# cs301_YourGroupNumber.net
KiCad netlist of a schematic drawn in Altium Designer
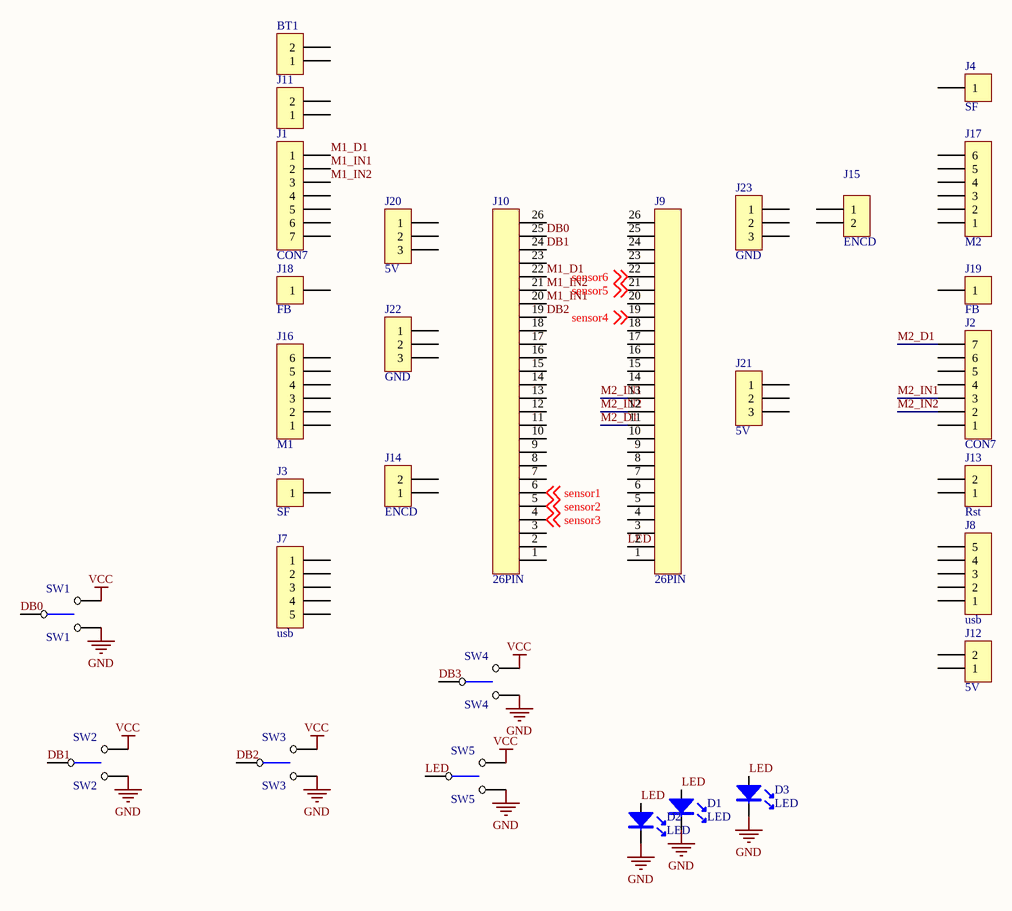
[diagram p0: cs301_YourGroupNumber.SchDoc]

(export (version "E")
  (design (tool "Eeschema 10.0.6"))
  (components
    (comp (ref "BT1")
      (value "Battery")
      (footprint "sip2")
      (description "Connector")
      (libsource (lib "") (part "CON2_1"))
    )
    (comp (ref "D1") (value "LED") (footprint "LED0.1/5MM") (libsource (lib "COMSYS301_2013") (part "LED")))
    (comp (ref "D2") (value "LED") (footprint "LED0.1/5MM") (libsource (lib "COMSYS301_2013") (part "LED")))
    (comp (ref "D3") (value "LED") (footprint "LED0.1/5MM") (libsource (lib "COMSYS301_2013") (part "LED")))
    (comp (ref "J1")
      (value "CON7")
      (footprint "SIP7")
      (description "Connector")
      (libsource (lib "Miscellaneous Devices") (part "CON7"))
    )
    (comp (ref "J2")
      (value "CON7")
      (footprint "SIP7")
      (description "Connector")
      (libsource (lib "") (part "CON7_1"))
    )
    (comp (ref "J3")
      (value "SF")
      (footprint "SIP1/0.6")
      (description "Connector")
      (libsource (lib "") (part "CON1_3"))
    )
    (comp (ref "J4")
      (value "SF")
      (footprint "SIP1/0.6")
      (description "Connector")
      (libsource (lib "") (part "CON1_1"))
    )
    (comp (ref "J7")
      (value "usb")
      (footprint "SIP5")
      (description "Connector")
      (libsource (lib "Miscellaneous Devices") (part "CON5"))
    )
    (comp (ref "J8")
      (value "usb")
      (footprint "SIP5")
      (description "Connector")
      (libsource (lib "") (part "CON5_1"))
    )
    (comp (ref "J9")
      (value "26PIN")
      (footprint "SIP26")
      (libsource (lib "Miscellaneous Devices") (part "26PIN"))
    )
    (comp (ref "J10") (value "26PIN") (footprint "SIP26") (libsource (lib "") (part "26PIN_1")))
    (comp (ref "J11")
      (value "Battery")
      (footprint "sip2")
      (description "Connector")
      (libsource (lib "") (part "CON2_1"))
    )
    (comp (ref "J12")
      (value "5V")
      (footprint "sip2")
      (description "Connector")
      (libsource (lib "") (part "CON2_2"))
    )
    (comp (ref "J13")
      (value "Rst")
      (footprint "sip2")
      (description "Connector")
      (libsource (lib "") (part "CON2_2"))
    )
    (comp (ref "J14")
      (value "ENCD")
      (footprint "sip2")
      (description "Connector")
      (libsource (lib "") (part "CON2_1"))
    )
    (comp (ref "J15")
      (value "ENCD")
      (footprint "sip2")
      (description "Connector")
      (libsource (lib "Miscellaneous Devices") (part "CON2"))
    )
    (comp (ref "J16")
      (value "M1")
      (footprint "sip6")
      (description "Connector")
      (libsource (lib "Miscellaneous Devices") (part "CON6"))
    )
    (comp (ref "J17")
      (value "M2")
      (footprint "sip6")
      (description "Connector")
      (libsource (lib "") (part "CON6_1"))
    )
    (comp (ref "J18")
      (value "FB")
      (footprint "SIP1/0.6")
      (description "Connector")
      (libsource (lib "") (part "CON1_2"))
    )
    (comp (ref "J19")
      (value "FB")
      (footprint "SIP1/0.6")
      (description "Connector")
      (libsource (lib "Miscellaneous Devices") (part "CON1"))
    )
    (comp (ref "J20")
      (value "5V")
      (footprint "sip3")
      (description "Connector")
      (libsource (lib "Miscellaneous Devices") (part "CON3"))
    )
    (comp (ref "J21")
      (value "5V")
      (footprint "sip3")
      (description "Connector")
      (libsource (lib "Miscellaneous Devices") (part "CON3"))
    )
    (comp (ref "J22")
      (value "GND")
      (footprint "sip3")
      (description "Connector")
      (libsource (lib "Miscellaneous Devices") (part "CON3"))
    )
    (comp (ref "J23")
      (value "GND")
      (footprint "sip3")
      (description "Connector")
      (libsource (lib "Miscellaneous Devices") (part "CON3"))
    )
    (comp (ref "SW1")
      (value "SW1")
      (footprint "SW-SPDT")
      (description "Toggle Switch")
      (libsource (lib "COMSYS301_2013") (part "SW-SPDT"))
    )
    (comp (ref "SW2")
      (value "SW2")
      (footprint "SW-SPDT")
      (description "Toggle Switch")
      (libsource (lib "COMSYS301_2013") (part "SW-SPDT"))
    )
    (comp (ref "SW3")
      (value "SW3")
      (footprint "SW-SPDT")
      (description "Toggle Switch")
      (libsource (lib "COMSYS301_2013") (part "SW-SPDT"))
    )
    (comp (ref "SW4")
      (value "SW4")
      (footprint "SW-SPDT")
      (description "Toggle Switch")
      (libsource (lib "COMSYS301_2013") (part "SW-SPDT"))
    )
    (comp (ref "SW5")
      (value "SW5")
      (footprint "SW-SPDT")
      (description "Toggle Switch")
      (libsource (lib "COMSYS301_2013") (part "SW-SPDT"))
    )
  )
  (nets
    (net (code "1") (name "/DB0") (class "Default")
      (node (ref "J10") (pin "25") (pinfunction "25_25") (pintype "passive"))
      (node (ref "SW1") (pin "2") (pinfunction "2_2") (pintype "passive"))
    )
    (net (code "2") (name "/DB1") (class "Default")
      (node (ref "J10") (pin "24") (pinfunction "24_24") (pintype "passive"))
      (node (ref "SW2") (pin "2") (pinfunction "2_2") (pintype "passive"))
    )
    (net (code "3") (name "/DB2") (class "Default")
      (node (ref "J10") (pin "19") (pinfunction "19_19") (pintype "passive"))
      (node (ref "SW3") (pin "2") (pinfunction "2_2") (pintype "passive"))
    )
    (net (code "4") (name "/DB3") (class "Default")
      (node (ref "SW4") (pin "2") (pinfunction "2_2") (pintype "passive"))
    )
    (net (code "5") (name "/LED") (class "Default")
      (node (ref "D1") (pin "A") (pinfunction "1_A") (pintype "passive"))
      (node (ref "D2") (pin "A") (pinfunction "1_A") (pintype "passive"))
      (node (ref "D3") (pin "A") (pinfunction "1_A") (pintype "passive"))
      (node (ref "J9") (pin "2") (pinfunction "2_2") (pintype "passive"))
      (node (ref "SW5") (pin "2") (pinfunction "2_2") (pintype "passive"))
    )
    (net (code "6") (name "/M1_D1") (class "Default")
      (node (ref "J1") (pin "1") (pinfunction "1_1") (pintype "passive"))
      (node (ref "J10") (pin "22") (pinfunction "22_22") (pintype "passive"))
    )
    (net (code "7") (name "/M1_IN1") (class "Default")
      (node (ref "J1") (pin "2") (pinfunction "2_2") (pintype "passive"))
      (node (ref "J10") (pin "20") (pinfunction "20_20") (pintype "passive"))
    )
    (net (code "8") (name "/M1_IN2") (class "Default")
      (node (ref "J1") (pin "3") (pinfunction "3_3") (pintype "passive"))
      (node (ref "J10") (pin "21") (pinfunction "21_21") (pintype "passive"))
    )
    (net (code "9") (name "/M2_D1") (class "Default")
      (node (ref "J2") (pin "7") (pinfunction "7_7") (pintype "passive"))
      (node (ref "J9") (pin "11") (pinfunction "11_11") (pintype "passive"))
    )
    (net (code "10") (name "/M2_IN1") (class "Default")
      (node (ref "J2") (pin "3") (pinfunction "3_3") (pintype "passive"))
      (node (ref "J9") (pin "13") (pinfunction "13_13") (pintype "passive"))
    )
    (net (code "11") (name "/M2_IN2") (class "Default")
      (node (ref "J2") (pin "2") (pinfunction "2_2") (pintype "passive"))
      (node (ref "J9") (pin "12") (pinfunction "12_12") (pintype "passive"))
    )
    (net (code "12") (name "GND") (class "Default")
      (node (ref "D1") (pin "K") (pinfunction "2_K") (pintype "passive"))
      (node (ref "D2") (pin "K") (pinfunction "2_K") (pintype "passive"))
      (node (ref "D3") (pin "K") (pinfunction "2_K") (pintype "passive"))
      (node (ref "SW1") (pin "3") (pinfunction "3_3") (pintype "passive"))
      (node (ref "SW2") (pin "3") (pinfunction "3_3") (pintype "passive"))
      (node (ref "SW3") (pin "3") (pinfunction "3_3") (pintype "passive"))
      (node (ref "SW4") (pin "3") (pinfunction "3_3") (pintype "passive"))
      (node (ref "SW5") (pin "3") (pinfunction "3_3") (pintype "passive"))
    )
    (net (code "13") (name "VCC") (class "Default")
      (node (ref "SW1") (pin "1") (pinfunction "1_1") (pintype "passive"))
      (node (ref "SW2") (pin "1") (pinfunction "1_1") (pintype "passive"))
      (node (ref "SW3") (pin "1") (pinfunction "1_1") (pintype "passive"))
      (node (ref "SW4") (pin "1") (pinfunction "1_1") (pintype "passive"))
      (node (ref "SW5") (pin "1") (pinfunction "1_1") (pintype "passive"))
    )
    (net (code "14") (name "sensor1") (class "Default")
      (node (ref "J10") (pin "6") (pinfunction "6_6") (pintype "passive"))
    )
    (net (code "15") (name "sensor2") (class "Default")
      (node (ref "J10") (pin "5") (pinfunction "5_5") (pintype "passive"))
    )
    (net (code "16") (name "sensor3") (class "Default")
      (node (ref "J10") (pin "4") (pinfunction "4_4") (pintype "passive"))
    )
    (net (code "17") (name "sensor4") (class "Default")
      (node (ref "J9") (pin "19") (pinfunction "19_19") (pintype "passive"))
    )
    (net (code "18") (name "sensor5") (class "Default")
      (node (ref "J9") (pin "21") (pinfunction "21_21") (pintype "passive"))
    )
    (net (code "19") (name "sensor6") (class "Default")
      (node (ref "J9") (pin "22") (pinfunction "22_22") (pintype "passive"))
    )
    (net (code "20") (name "unconnected-(BT1-Pad1)") (class "Default")
      (node (ref "BT1") (pin "1") (pinfunction "1_1") (pintype "passive"))
    )
    (net (code "21") (name "unconnected-(BT1-Pad2)") (class "Default")
      (node (ref "BT1") (pin "2") (pinfunction "2_2") (pintype "passive"))
    )
    (net (code "22") (name "unconnected-(J1-Pad4)") (class "Default")
      (node (ref "J1") (pin "4") (pinfunction "4_4") (pintype "passive"))
    )
    (net (code "23") (name "unconnected-(J1-Pad5)") (class "Default")
      (node (ref "J1") (pin "5") (pinfunction "5_5") (pintype "passive"))
    )
    (net (code "24") (name "unconnected-(J1-Pad6)") (class "Default")
      (node (ref "J1") (pin "6") (pinfunction "6_6") (pintype "passive"))
    )
    (net (code "25") (name "unconnected-(J1-Pad7)") (class "Default")
      (node (ref "J1") (pin "7") (pinfunction "7_7") (pintype "passive"))
    )
    (net (code "26") (name "unconnected-(J2-Pad1)") (class "Default")
      (node (ref "J2") (pin "1") (pinfunction "1_1") (pintype "passive"))
    )
    (net (code "27") (name "unconnected-(J2-Pad4)") (class "Default")
      (node (ref "J2") (pin "4") (pinfunction "4_4") (pintype "passive"))
    )
    (net (code "28") (name "unconnected-(J2-Pad5)") (class "Default")
      (node (ref "J2") (pin "5") (pinfunction "5_5") (pintype "passive"))
    )
    (net (code "29") (name "unconnected-(J2-Pad6)") (class "Default")
      (node (ref "J2") (pin "6") (pinfunction "6_6") (pintype "passive"))
    )
    (net (code "30") (name "unconnected-(J3-Pad1)") (class "Default")
      (node (ref "J3") (pin "1") (pinfunction "1_1") (pintype "passive"))
    )
    (net (code "31") (name "unconnected-(J4-Pad1)") (class "Default")
      (node (ref "J4") (pin "1") (pinfunction "1_1") (pintype "passive"))
    )
    (net (code "32") (name "unconnected-(J7-Pad1)") (class "Default")
      (node (ref "J7") (pin "1") (pinfunction "1_1") (pintype "passive"))
    )
    (net (code "33") (name "unconnected-(J7-Pad2)") (class "Default")
      (node (ref "J7") (pin "2") (pinfunction "2_2") (pintype "passive"))
    )
    (net (code "34") (name "unconnected-(J7-Pad3)") (class "Default")
      (node (ref "J7") (pin "3") (pinfunction "3_3") (pintype "passive"))
    )
    (net (code "35") (name "unconnected-(J7-Pad4)") (class "Default")
      (node (ref "J7") (pin "4") (pinfunction "4_4") (pintype "passive"))
    )
    (net (code "36") (name "unconnected-(J7-Pad5)") (class "Default")
      (node (ref "J7") (pin "5") (pinfunction "5_5") (pintype "passive"))
    )
    (net (code "37") (name "unconnected-(J8-Pad1)") (class "Default")
      (node (ref "J8") (pin "1") (pinfunction "1_1") (pintype "passive"))
    )
    (net (code "38") (name "unconnected-(J8-Pad2)") (class "Default")
      (node (ref "J8") (pin "2") (pinfunction "2_2") (pintype "passive"))
    )
    (net (code "39") (name "unconnected-(J8-Pad3)") (class "Default")
      (node (ref "J8") (pin "3") (pinfunction "3_3") (pintype "passive"))
    )
    (net (code "40") (name "unconnected-(J8-Pad4)") (class "Default")
      (node (ref "J8") (pin "4") (pinfunction "4_4") (pintype "passive"))
    )
    (net (code "41") (name "unconnected-(J8-Pad5)") (class "Default")
      (node (ref "J8") (pin "5") (pinfunction "5_5") (pintype "passive"))
    )
    (net (code "42") (name "unconnected-(J9-Pad1)") (class "Default")
      (node (ref "J9") (pin "1") (pinfunction "1_1") (pintype "passive"))
    )
    (net (code "43") (name "unconnected-(J9-Pad3)") (class "Default")
      (node (ref "J9") (pin "3") (pinfunction "3_3") (pintype "passive"))
    )
    (net (code "44") (name "unconnected-(J9-Pad4)") (class "Default")
      (node (ref "J9") (pin "4") (pinfunction "4_4") (pintype "passive"))
    )
    (net (code "45") (name "unconnected-(J9-Pad5)") (class "Default")
      (node (ref "J9") (pin "5") (pinfunction "5_5") (pintype "passive"))
    )
    (net (code "46") (name "unconnected-(J9-Pad6)") (class "Default")
      (node (ref "J9") (pin "6") (pinfunction "6_6") (pintype "passive"))
    )
    (net (code "47") (name "unconnected-(J9-Pad7)") (class "Default")
      (node (ref "J9") (pin "7") (pinfunction "7_7") (pintype "passive"))
    )
    (net (code "48") (name "unconnected-(J9-Pad8)") (class "Default")
      (node (ref "J9") (pin "8") (pinfunction "8_8") (pintype "passive"))
    )
    (net (code "49") (name "unconnected-(J9-Pad9)") (class "Default")
      (node (ref "J9") (pin "9") (pinfunction "9_9") (pintype "passive"))
    )
    (net (code "50") (name "unconnected-(J9-Pad10)") (class "Default")
      (node (ref "J9") (pin "10") (pinfunction "10_10") (pintype "passive"))
    )
    (net (code "51") (name "unconnected-(J9-Pad14)") (class "Default")
      (node (ref "J9") (pin "14") (pinfunction "14_14") (pintype "passive"))
    )
    (net (code "52") (name "unconnected-(J9-Pad15)") (class "Default")
      (node (ref "J9") (pin "15") (pinfunction "15_15") (pintype "passive"))
    )
    (net (code "53") (name "unconnected-(J9-Pad16)") (class "Default")
      (node (ref "J9") (pin "16") (pinfunction "16_16") (pintype "passive"))
    )
    (net (code "54") (name "unconnected-(J9-Pad17)") (class "Default")
      (node (ref "J9") (pin "17") (pinfunction "17_17") (pintype "passive"))
    )
    (net (code "55") (name "unconnected-(J9-Pad18)") (class "Default")
      (node (ref "J9") (pin "18") (pinfunction "18_18") (pintype "passive"))
    )
    (net (code "56") (name "unconnected-(J9-Pad20)") (class "Default")
      (node (ref "J9") (pin "20") (pinfunction "20_20") (pintype "passive"))
    )
    (net (code "57") (name "unconnected-(J9-Pad23)") (class "Default")
      (node (ref "J9") (pin "23") (pinfunction "23_23") (pintype "passive"))
    )
    (net (code "58") (name "unconnected-(J9-Pad24)") (class "Default")
      (node (ref "J9") (pin "24") (pinfunction "24_24") (pintype "passive"))
    )
    (net (code "59") (name "unconnected-(J9-Pad25)") (class "Default")
      (node (ref "J9") (pin "25") (pinfunction "25_25") (pintype "passive"))
    )
    (net (code "60") (name "unconnected-(J9-Pad26)") (class "Default")
      (node (ref "J9") (pin "26") (pinfunction "26_26") (pintype "passive"))
    )
    (net (code "61") (name "unconnected-(J10-Pad1)") (class "Default")
      (node (ref "J10") (pin "1") (pinfunction "1_1") (pintype "passive"))
    )
    (net (code "62") (name "unconnected-(J10-Pad2)") (class "Default")
      (node (ref "J10") (pin "2") (pinfunction "2_2") (pintype "passive"))
    )
    (net (code "63") (name "unconnected-(J10-Pad3)") (class "Default")
      (node (ref "J10") (pin "3") (pinfunction "3_3") (pintype "passive"))
    )
    (net (code "64") (name "unconnected-(J10-Pad7)") (class "Default")
      (node (ref "J10") (pin "7") (pinfunction "7_7") (pintype "passive"))
    )
    (net (code "65") (name "unconnected-(J10-Pad8)") (class "Default")
      (node (ref "J10") (pin "8") (pinfunction "8_8") (pintype "passive"))
    )
    (net (code "66") (name "unconnected-(J10-Pad9)") (class "Default")
      (node (ref "J10") (pin "9") (pinfunction "9_9") (pintype "passive"))
    )
    (net (code "67") (name "unconnected-(J10-Pad10)") (class "Default")
      (node (ref "J10") (pin "10") (pinfunction "10_10") (pintype "passive"))
    )
    (net (code "68") (name "unconnected-(J10-Pad11)") (class "Default")
      (node (ref "J10") (pin "11") (pinfunction "11_11") (pintype "passive"))
    )
    (net (code "69") (name "unconnected-(J10-Pad12)") (class "Default")
      (node (ref "J10") (pin "12") (pinfunction "12_12") (pintype "passive"))
    )
    (net (code "70") (name "unconnected-(J10-Pad13)") (class "Default")
      (node (ref "J10") (pin "13") (pinfunction "13_13") (pintype "passive"))
    )
    (net (code "71") (name "unconnected-(J10-Pad14)") (class "Default")
      (node (ref "J10") (pin "14") (pinfunction "14_14") (pintype "passive"))
    )
    (net (code "72") (name "unconnected-(J10-Pad15)") (class "Default")
      (node (ref "J10") (pin "15") (pinfunction "15_15") (pintype "passive"))
    )
    (net (code "73") (name "unconnected-(J10-Pad16)") (class "Default")
      (node (ref "J10") (pin "16") (pinfunction "16_16") (pintype "passive"))
    )
    (net (code "74") (name "unconnected-(J10-Pad17)") (class "Default")
      (node (ref "J10") (pin "17") (pinfunction "17_17") (pintype "passive"))
    )
    (net (code "75") (name "unconnected-(J10-Pad18)") (class "Default")
      (node (ref "J10") (pin "18") (pinfunction "18_18") (pintype "passive"))
    )
    (net (code "76") (name "unconnected-(J10-Pad23)") (class "Default")
      (node (ref "J10") (pin "23") (pinfunction "23_23") (pintype "passive"))
    )
    (net (code "77") (name "unconnected-(J10-Pad26)") (class "Default")
      (node (ref "J10") (pin "26") (pinfunction "26_26") (pintype "passive"))
    )
    (net (code "78") (name "unconnected-(J11-Pad1)") (class "Default")
      (node (ref "J11") (pin "1") (pinfunction "1_1") (pintype "passive"))
    )
    (net (code "79") (name "unconnected-(J11-Pad2)") (class "Default")
      (node (ref "J11") (pin "2") (pinfunction "2_2") (pintype "passive"))
    )
    (net (code "80") (name "unconnected-(J12-Pad1)") (class "Default")
      (node (ref "J12") (pin "1") (pinfunction "1_1") (pintype "passive"))
    )
    (net (code "81") (name "unconnected-(J12-Pad2)") (class "Default")
      (node (ref "J12") (pin "2") (pinfunction "2_2") (pintype "passive"))
    )
    (net (code "82") (name "unconnected-(J13-Pad1)") (class "Default")
      (node (ref "J13") (pin "1") (pinfunction "1_1") (pintype "passive"))
    )
    (net (code "83") (name "unconnected-(J13-Pad2)") (class "Default")
      (node (ref "J13") (pin "2") (pinfunction "2_2") (pintype "passive"))
    )
    (net (code "84") (name "unconnected-(J14-Pad1)") (class "Default")
      (node (ref "J14") (pin "1") (pinfunction "1_1") (pintype "passive"))
    )
    (net (code "85") (name "unconnected-(J14-Pad2)") (class "Default")
      (node (ref "J14") (pin "2") (pinfunction "2_2") (pintype "passive"))
    )
    (net (code "86") (name "unconnected-(J15-Pad1)") (class "Default")
      (node (ref "J15") (pin "1") (pinfunction "1_1") (pintype "passive"))
    )
    (net (code "87") (name "unconnected-(J15-Pad2)") (class "Default")
      (node (ref "J15") (pin "2") (pinfunction "2_2") (pintype "passive"))
    )
    (net (code "88") (name "unconnected-(J16-Pad1)") (class "Default")
      (node (ref "J16") (pin "1") (pinfunction "1_1") (pintype "passive"))
    )
    (net (code "89") (name "unconnected-(J16-Pad2)") (class "Default")
      (node (ref "J16") (pin "2") (pinfunction "2_2") (pintype "passive"))
    )
    (net (code "90") (name "unconnected-(J16-Pad3)") (class "Default")
      (node (ref "J16") (pin "3") (pinfunction "3_3") (pintype "passive"))
    )
    (net (code "91") (name "unconnected-(J16-Pad4)") (class "Default")
      (node (ref "J16") (pin "4") (pinfunction "4_4") (pintype "passive"))
    )
    (net (code "92") (name "unconnected-(J16-Pad5)") (class "Default")
      (node (ref "J16") (pin "5") (pinfunction "5_5") (pintype "passive"))
    )
    (net (code "93") (name "unconnected-(J16-Pad6)") (class "Default")
      (node (ref "J16") (pin "6") (pinfunction "6_6") (pintype "passive"))
    )
    (net (code "94") (name "unconnected-(J17-Pad1)") (class "Default")
      (node (ref "J17") (pin "1") (pinfunction "1_1") (pintype "passive"))
    )
    (net (code "95") (name "unconnected-(J17-Pad2)") (class "Default")
      (node (ref "J17") (pin "2") (pinfunction "2_2") (pintype "passive"))
    )
    (net (code "96") (name "unconnected-(J17-Pad3)") (class "Default")
      (node (ref "J17") (pin "3") (pinfunction "3_3") (pintype "passive"))
    )
    (net (code "97") (name "unconnected-(J17-Pad4)") (class "Default")
      (node (ref "J17") (pin "4") (pinfunction "4_4") (pintype "passive"))
    )
    (net (code "98") (name "unconnected-(J17-Pad5)") (class "Default")
      (node (ref "J17") (pin "5") (pinfunction "5_5") (pintype "passive"))
    )
    (net (code "99") (name "unconnected-(J17-Pad6)") (class "Default")
      (node (ref "J17") (pin "6") (pinfunction "6_6") (pintype "passive"))
    )
    (net (code "100") (name "unconnected-(J18-Pad1)") (class "Default")
      (node (ref "J18") (pin "1") (pinfunction "1_1") (pintype "passive"))
    )
    (net (code "101") (name "unconnected-(J19-Pad1)") (class "Default")
      (node (ref "J19") (pin "1") (pinfunction "1_1") (pintype "passive"))
    )
    (net (code "102") (name "unconnected-(J20-Pad1)") (class "Default")
      (node (ref "J20") (pin "1") (pinfunction "1_1") (pintype "passive"))
    )
    (net (code "103") (name "unconnected-(J20-Pad2)") (class "Default")
      (node (ref "J20") (pin "2") (pinfunction "2_2") (pintype "passive"))
    )
    (net (code "104") (name "unconnected-(J20-Pad3)") (class "Default")
      (node (ref "J20") (pin "3") (pinfunction "3_3") (pintype "passive"))
    )
    (net (code "105") (name "unconnected-(J21-Pad1)") (class "Default")
      (node (ref "J21") (pin "1") (pinfunction "1_1") (pintype "passive"))
    )
    (net (code "106") (name "unconnected-(J21-Pad2)") (class "Default")
      (node (ref "J21") (pin "2") (pinfunction "2_2") (pintype "passive"))
    )
    (net (code "107") (name "unconnected-(J21-Pad3)") (class "Default")
      (node (ref "J21") (pin "3") (pinfunction "3_3") (pintype "passive"))
    )
    (net (code "108") (name "unconnected-(J22-Pad1)") (class "Default")
      (node (ref "J22") (pin "1") (pinfunction "1_1") (pintype "passive"))
    )
    (net (code "109") (name "unconnected-(J22-Pad2)") (class "Default")
      (node (ref "J22") (pin "2") (pinfunction "2_2") (pintype "passive"))
    )
    (net (code "110") (name "unconnected-(J22-Pad3)") (class "Default")
      (node (ref "J22") (pin "3") (pinfunction "3_3") (pintype "passive"))
    )
    (net (code "111") (name "unconnected-(J23-Pad1)") (class "Default")
      (node (ref "J23") (pin "1") (pinfunction "1_1") (pintype "passive"))
    )
    (net (code "112") (name "unconnected-(J23-Pad2)") (class "Default")
      (node (ref "J23") (pin "2") (pinfunction "2_2") (pintype "passive"))
    )
    (net (code "113") (name "unconnected-(J23-Pad3)") (class "Default")
      (node (ref "J23") (pin "3") (pinfunction "3_3") (pintype "passive"))
    )
  )
)
